# esquematico_prototipo.net
KiCad netlist of a schematic drawn in Altium Designer
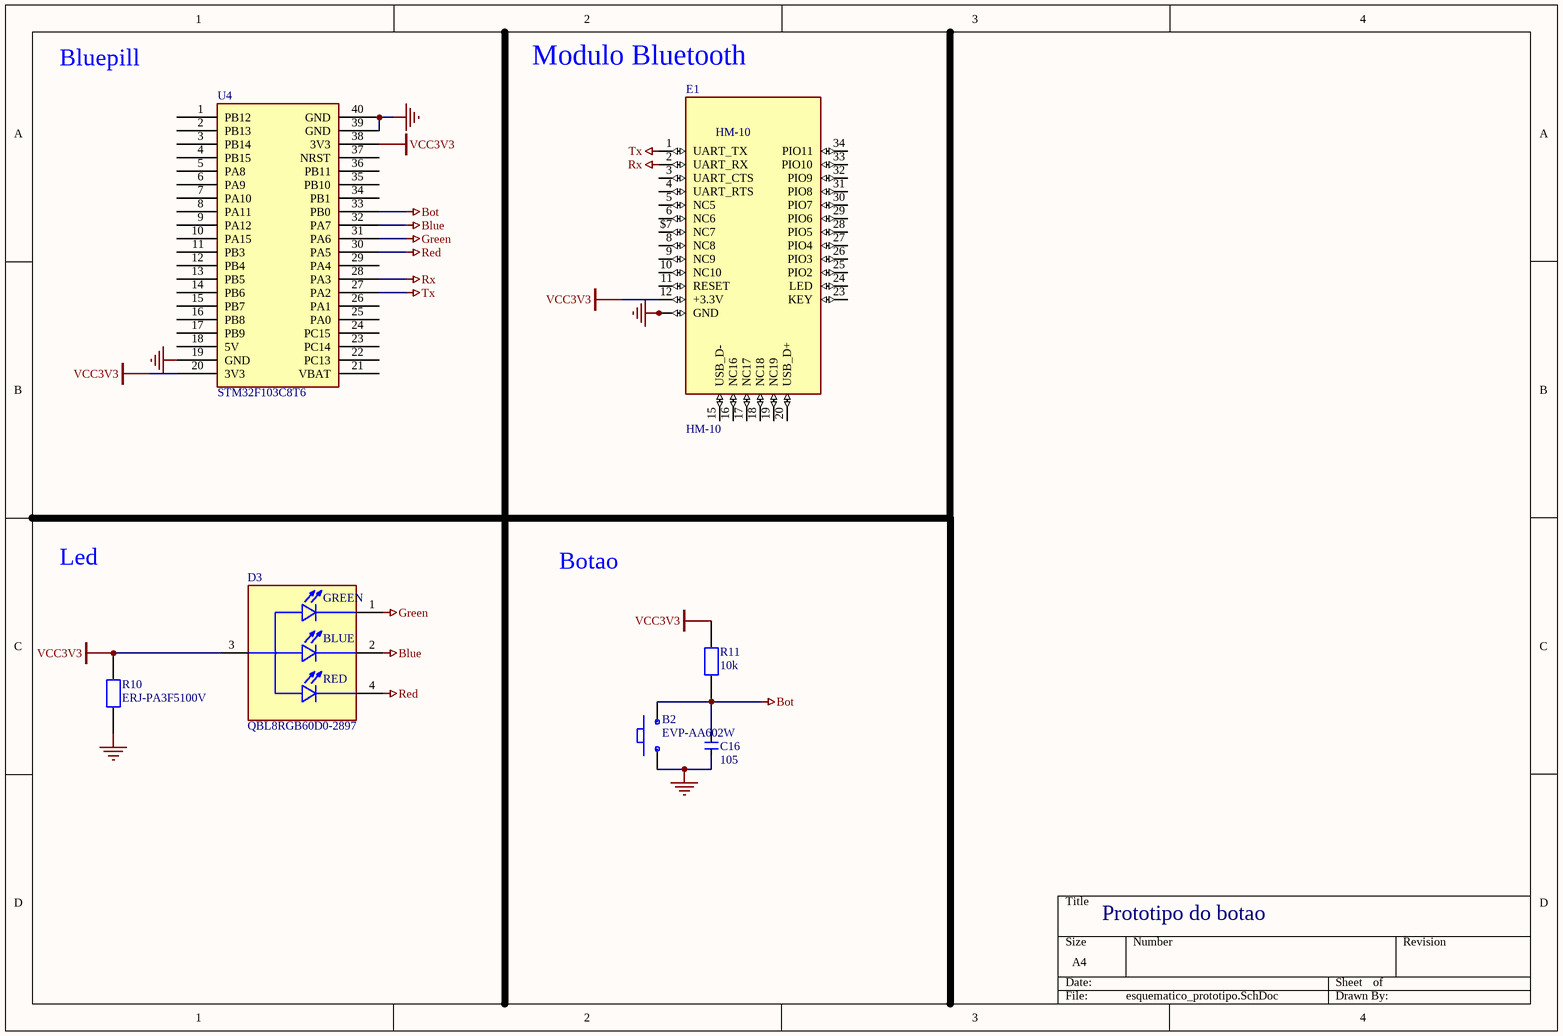
[diagram p0: esquematico_prototipo.SchDoc]

(export (version "E")
  (design (tool "Eeschema 10.0.6"))
  (components
    (comp (ref "B2")
      (value "EVP-AA602W")
      (footprint "botao")
      (description "Switch Tactile N.O. SPST Rectangular Button J-Bend 0.02A 15VDC 3.5N SMD Embossed T/R")
      (fields (field (name "MANUFACTURER") "Panasonic"))
      (libsource (lib "bluepill") (part "EVP-AA602W"))
    )
    (comp (ref "C16")
      (value "105")
      (footprint "C_1µF_10V")
      (description "10V 1uF X7R ±10% 0603 Multilayer Ceramic Capacitors MLCC - SMD/SMT ROHS")
      (fields
        (field (name "MANUFACTURER") "Samsung Electro-Mechanics")
        (field (name "MANUFACTURER PART NUMBER") "CL10B105KP8NNNC")
      )
      (libsource (lib "bluepill") (part "CL10B105KP8NNNC"))
    )
    (comp (ref "D3")
      (value "QBL8RGB60D0-2897")
      (footprint "LED_QBL8RGB60D0-2897")
      (fields (field (name "MF") "QT Brightek (QTB)"))
      (libsource (lib "PrototipoBotao") (part "QBL8RGB60D0-2897"))
    )
    (comp (ref "E1")
      (value "HM-10")
      (footprint "26.9X13X2.2_BOARD")
      (description "Bluetooth 4.0 module with 4pin base board that can support iphone4s or later.")
      (fields (field (name "MF") "Jinan Huamao Technology"))
      (libsource (lib "PrototipoBotao") (part "HM-10"))
    )
    (comp (ref "R10")
      (value "ERJ-PA3F5100V")
      (footprint "R_0603_510")
      (description "Res Thick Film 0603 510 Ohm 1% 0.25W(1/4W) +/-100ppm/C Molded SMD Automotive Punched T/R")
      (fields (field (name "MANUFACTURER") "Panasonic") (field (name "TOLERANCE") "1%"))
      (libsource (lib "PrototipoBotao") (part "ERJ-PA3F5100V"))
    )
    (comp (ref "R11")
      (value "10k")
      (footprint "R_0603_10K")
      (description "Res Thick Film 0603 10K Ohm 1% 0.25W(1/4W) ±100ppm/C Pad SMD Automotive T/R")
      (fields
        (field (name "MANUFACTURER") "Panasonic")
        (field (name "MANUFACTURER PART NUMBER") "ERJPA3F1002V")
      )
      (libsource (lib "bluepill") (part "ERJPA3F1002V"))
    )
    (comp (ref "U4")
      (value "STM32F103C8T6")
      (footprint "Stm32 BluePill")
      (description "Designed By @Alixahedi")
      (libsource (lib "PrototipoBotao") (part "BluePill"))
    )
  )
  (nets
    (net (code "1") (name "Blue") (class "Default")
      (node (ref "D3") (pin "2") (pinfunction "CATHODE_BLUE_2") (pintype "passive"))
      (node (ref "U4") (pin "32") (pinfunction "PA7_32") (pintype "passive"))
    )
    (net (code "2") (name "Bot") (class "Default")
      (node (ref "B2") (pin "1") (pinfunction "1_1") (pintype "passive"))
      (node (ref "C16") (pin "1") (pinfunction "1_1") (pintype "passive"))
      (node (ref "R11") (pin "1") (pinfunction "1_1") (pintype "passive"))
      (node (ref "U4") (pin "33") (pinfunction "PB0_33") (pintype "passive"))
    )
    (net (code "3") (name "GND") (class "Default")
      (node (ref "B2") (pin "2") (pinfunction "2_2") (pintype "passive"))
      (node (ref "C16") (pin "2") (pinfunction "2_2") (pintype "passive"))
      (node (ref "E1") (pin "13") (pinfunction "GND_13") (pintype "bidirectional"))
      (node (ref "E1") (pin "14") (pinfunction "GND_14") (pintype "bidirectional"))
      (node (ref "E1") (pin "21") (pinfunction "GND_21") (pintype "bidirectional"))
      (node (ref "E1") (pin "22") (pinfunction "GND_22") (pintype "bidirectional"))
      (node (ref "R10") (pin "1") (pinfunction "1_1") (pintype "passive"))
      (node (ref "U4") (pin "19") (pinfunction "GND_19") (pintype "passive"))
      (node (ref "U4") (pin "39") (pinfunction "GND_39") (pintype "passive"))
      (node (ref "U4") (pin "40") (pinfunction "GND_40") (pintype "passive"))
    )
    (net (code "4") (name "Green") (class "Default")
      (node (ref "D3") (pin "1") (pinfunction "CATHODE_GREEN_1") (pintype "passive"))
      (node (ref "U4") (pin "31") (pinfunction "PA6_31") (pintype "passive"))
    )
    (net (code "5") (name "Red") (class "Default")
      (node (ref "D3") (pin "4") (pinfunction "CATHODE_RED_4") (pintype "passive"))
      (node (ref "U4") (pin "30") (pinfunction "PA5_30") (pintype "passive"))
    )
    (net (code "6") (name "Rx") (class "Default")
      (node (ref "E1") (pin "2") (pinfunction "UART_RX_2") (pintype "bidirectional"))
      (node (ref "U4") (pin "28") (pinfunction "PA3_28") (pintype "passive"))
    )
    (net (code "7") (name "Tx") (class "Default")
      (node (ref "E1") (pin "1") (pinfunction "UART_TX_1") (pintype "bidirectional"))
      (node (ref "U4") (pin "27") (pinfunction "PA2_27") (pintype "passive"))
    )
    (net (code "8") (name "VCC3V3") (class "Default")
      (node (ref "D3") (pin "3") (pinfunction "COMMON_ANODE_3") (pintype "passive"))
      (node (ref "E1") (pin "12") (pinfunction "+3.3V_12") (pintype "bidirectional"))
      (node (ref "R10") (pin "2") (pinfunction "2_2") (pintype "passive"))
      (node (ref "R11") (pin "2") (pinfunction "2_2") (pintype "passive"))
      (node (ref "U4") (pin "20") (pinfunction "3V3_20") (pintype "passive"))
      (node (ref "U4") (pin "38") (pinfunction "3V3_38") (pintype "passive"))
    )
    (net (code "9") (name "unconnected-(E1-KEY-Pad23)") (class "Default")
      (node (ref "E1") (pin "23") (pinfunction "KEY_23") (pintype "bidirectional"))
    )
    (net (code "10") (name "unconnected-(E1-LED-Pad24)") (class "Default")
      (node (ref "E1") (pin "24") (pinfunction "LED_24") (pintype "bidirectional"))
    )
    (net (code "11") (name "unconnected-(E1-NC5-Pad5)") (class "Default")
      (node (ref "E1") (pin "5") (pinfunction "NC5_5") (pintype "bidirectional"))
    )
    (net (code "12") (name "unconnected-(E1-NC6-Pad6)") (class "Default")
      (node (ref "E1") (pin "6") (pinfunction "NC6_6") (pintype "bidirectional"))
    )
    (net (code "13") (name "unconnected-(E1-NC7-Pad$7)") (class "Default")
      (node (ref "E1") (pin "$7") (pinfunction "NC7_$7") (pintype "bidirectional"))
    )
    (net (code "14") (name "unconnected-(E1-NC8-Pad8)") (class "Default")
      (node (ref "E1") (pin "8") (pinfunction "NC8_8") (pintype "bidirectional"))
    )
    (net (code "15") (name "unconnected-(E1-NC9-Pad9)") (class "Default")
      (node (ref "E1") (pin "9") (pinfunction "NC9_9") (pintype "bidirectional"))
    )
    (net (code "16") (name "unconnected-(E1-NC10-Pad10)") (class "Default")
      (node (ref "E1") (pin "10") (pinfunction "NC10_10") (pintype "bidirectional"))
    )
    (net (code "17") (name "unconnected-(E1-NC16-Pad16)") (class "Default")
      (node (ref "E1") (pin "16") (pinfunction "NC16_16") (pintype "bidirectional"))
    )
    (net (code "18") (name "unconnected-(E1-NC17-Pad17)") (class "Default")
      (node (ref "E1") (pin "17") (pinfunction "NC17_17") (pintype "bidirectional"))
    )
    (net (code "19") (name "unconnected-(E1-NC18-Pad18)") (class "Default")
      (node (ref "E1") (pin "18") (pinfunction "NC18_18") (pintype "bidirectional"))
    )
    (net (code "20") (name "unconnected-(E1-NC19-Pad19)") (class "Default")
      (node (ref "E1") (pin "19") (pinfunction "NC19_19") (pintype "bidirectional"))
    )
    (net (code "21") (name "unconnected-(E1-PIO2-Pad25)") (class "Default")
      (node (ref "E1") (pin "25") (pinfunction "PIO2_25") (pintype "bidirectional"))
    )
    (net (code "22") (name "unconnected-(E1-PIO3-Pad26)") (class "Default")
      (node (ref "E1") (pin "26") (pinfunction "PIO3_26") (pintype "bidirectional"))
    )
    (net (code "23") (name "unconnected-(E1-PIO4-Pad27)") (class "Default")
      (node (ref "E1") (pin "27") (pinfunction "PIO4_27") (pintype "bidirectional"))
    )
    (net (code "24") (name "unconnected-(E1-PIO5-Pad28)") (class "Default")
      (node (ref "E1") (pin "28") (pinfunction "PIO5_28") (pintype "bidirectional"))
    )
    (net (code "25") (name "unconnected-(E1-PIO6-Pad29)") (class "Default")
      (node (ref "E1") (pin "29") (pinfunction "PIO6_29") (pintype "bidirectional"))
    )
    (net (code "26") (name "unconnected-(E1-PIO7-Pad30)") (class "Default")
      (node (ref "E1") (pin "30") (pinfunction "PIO7_30") (pintype "bidirectional"))
    )
    (net (code "27") (name "unconnected-(E1-PIO8-Pad31)") (class "Default")
      (node (ref "E1") (pin "31") (pinfunction "PIO8_31") (pintype "bidirectional"))
    )
    (net (code "28") (name "unconnected-(E1-PIO9-Pad32)") (class "Default")
      (node (ref "E1") (pin "32") (pinfunction "PIO9_32") (pintype "bidirectional"))
    )
    (net (code "29") (name "unconnected-(E1-PIO10-Pad33)") (class "Default")
      (node (ref "E1") (pin "33") (pinfunction "PIO10_33") (pintype "bidirectional"))
    )
    (net (code "30") (name "unconnected-(E1-PIO11-Pad34)") (class "Default")
      (node (ref "E1") (pin "34") (pinfunction "PIO11_34") (pintype "bidirectional"))
    )
    (net (code "31") (name "unconnected-(E1-RESET-Pad11)") (class "Default")
      (node (ref "E1") (pin "11") (pinfunction "RESET_11") (pintype "bidirectional"))
    )
    (net (code "32") (name "unconnected-(E1-UART_CTS-Pad3)") (class "Default")
      (node (ref "E1") (pin "3") (pinfunction "UART_CTS_3") (pintype "bidirectional"))
    )
    (net (code "33") (name "unconnected-(E1-UART_RTS-Pad4)") (class "Default")
      (node (ref "E1") (pin "4") (pinfunction "UART_RTS_4") (pintype "bidirectional"))
    )
    (net (code "34") (name "unconnected-(E1-USB_D+-Pad20)") (class "Default")
      (node (ref "E1") (pin "20") (pinfunction "USB_D+_20") (pintype "bidirectional"))
    )
    (net (code "35") (name "unconnected-(E1-USB_D--Pad15)") (class "Default")
      (node (ref "E1") (pin "15") (pinfunction "USB_D-_15") (pintype "bidirectional"))
    )
    (net (code "36") (name "unconnected-(U4-5V-Pad18)") (class "Default")
      (node (ref "U4") (pin "18") (pinfunction "5V_18") (pintype "passive"))
    )
    (net (code "37") (name "unconnected-(U4-NRST-Pad37)") (class "Default")
      (node (ref "U4") (pin "37") (pinfunction "NRST_37") (pintype "passive"))
    )
    (net (code "38") (name "unconnected-(U4-PA0-Pad25)") (class "Default")
      (node (ref "U4") (pin "25") (pinfunction "PA0_25") (pintype "passive"))
    )
    (net (code "39") (name "unconnected-(U4-PA1-Pad26)") (class "Default")
      (node (ref "U4") (pin "26") (pinfunction "PA1_26") (pintype "passive"))
    )
    (net (code "40") (name "unconnected-(U4-PA4-Pad29)") (class "Default")
      (node (ref "U4") (pin "29") (pinfunction "PA4_29") (pintype "passive"))
    )
    (net (code "41") (name "unconnected-(U4-PA8-Pad5)") (class "Default")
      (node (ref "U4") (pin "5") (pinfunction "PA8_5") (pintype "passive"))
    )
    (net (code "42") (name "unconnected-(U4-PA9-Pad6)") (class "Default")
      (node (ref "U4") (pin "6") (pinfunction "PA9_6") (pintype "passive"))
    )
    (net (code "43") (name "unconnected-(U4-PA10-Pad7)") (class "Default")
      (node (ref "U4") (pin "7") (pinfunction "PA10_7") (pintype "passive"))
    )
    (net (code "44") (name "unconnected-(U4-PA11-Pad8)") (class "Default")
      (node (ref "U4") (pin "8") (pinfunction "PA11_8") (pintype "passive"))
    )
    (net (code "45") (name "unconnected-(U4-PA12-Pad9)") (class "Default")
      (node (ref "U4") (pin "9") (pinfunction "PA12_9") (pintype "passive"))
    )
    (net (code "46") (name "unconnected-(U4-PA15-Pad10)") (class "Default")
      (node (ref "U4") (pin "10") (pinfunction "PA15_10") (pintype "passive"))
    )
    (net (code "47") (name "unconnected-(U4-PB1-Pad34)") (class "Default")
      (node (ref "U4") (pin "34") (pinfunction "PB1_34") (pintype "passive"))
    )
    (net (code "48") (name "unconnected-(U4-PB3-Pad11)") (class "Default")
      (node (ref "U4") (pin "11") (pinfunction "PB3_11") (pintype "passive"))
    )
    (net (code "49") (name "unconnected-(U4-PB4-Pad12)") (class "Default")
      (node (ref "U4") (pin "12") (pinfunction "PB4_12") (pintype "passive"))
    )
    (net (code "50") (name "unconnected-(U4-PB5-Pad13)") (class "Default")
      (node (ref "U4") (pin "13") (pinfunction "PB5_13") (pintype "passive"))
    )
    (net (code "51") (name "unconnected-(U4-PB6-Pad14)") (class "Default")
      (node (ref "U4") (pin "14") (pinfunction "PB6_14") (pintype "passive"))
    )
    (net (code "52") (name "unconnected-(U4-PB7-Pad15)") (class "Default")
      (node (ref "U4") (pin "15") (pinfunction "PB7_15") (pintype "passive"))
    )
    (net (code "53") (name "unconnected-(U4-PB8-Pad16)") (class "Default")
      (node (ref "U4") (pin "16") (pinfunction "PB8_16") (pintype "passive"))
    )
    (net (code "54") (name "unconnected-(U4-PB9-Pad17)") (class "Default")
      (node (ref "U4") (pin "17") (pinfunction "PB9_17") (pintype "passive"))
    )
    (net (code "55") (name "unconnected-(U4-PB10-Pad35)") (class "Default")
      (node (ref "U4") (pin "35") (pinfunction "PB10_35") (pintype "passive"))
    )
    (net (code "56") (name "unconnected-(U4-PB11-Pad36)") (class "Default")
      (node (ref "U4") (pin "36") (pinfunction "PB11_36") (pintype "passive"))
    )
    (net (code "57") (name "unconnected-(U4-PB12-Pad1)") (class "Default")
      (node (ref "U4") (pin "1") (pinfunction "PB12_1") (pintype "passive"))
    )
    (net (code "58") (name "unconnected-(U4-PB13-Pad2)") (class "Default")
      (node (ref "U4") (pin "2") (pinfunction "PB13_2") (pintype "passive"))
    )
    (net (code "59") (name "unconnected-(U4-PB14-Pad3)") (class "Default")
      (node (ref "U4") (pin "3") (pinfunction "PB14_3") (pintype "passive"))
    )
    (net (code "60") (name "unconnected-(U4-PB15-Pad4)") (class "Default")
      (node (ref "U4") (pin "4") (pinfunction "PB15_4") (pintype "passive"))
    )
    (net (code "61") (name "unconnected-(U4-PC13-Pad22)") (class "Default")
      (node (ref "U4") (pin "22") (pinfunction "PC13_22") (pintype "passive"))
    )
    (net (code "62") (name "unconnected-(U4-PC14-Pad23)") (class "Default")
      (node (ref "U4") (pin "23") (pinfunction "PC14_23") (pintype "passive"))
    )
    (net (code "63") (name "unconnected-(U4-PC15-Pad24)") (class "Default")
      (node (ref "U4") (pin "24") (pinfunction "PC15_24") (pintype "passive"))
    )
    (net (code "64") (name "unconnected-(U4-VBAT-Pad21)") (class "Default")
      (node (ref "U4") (pin "21") (pinfunction "VBAT_21") (pintype "passive"))
    )
  )
)
